# arduino_Uno_STIM_ShieldII_v4.net
KiCad netlist of a schematic drawn in EAGLE
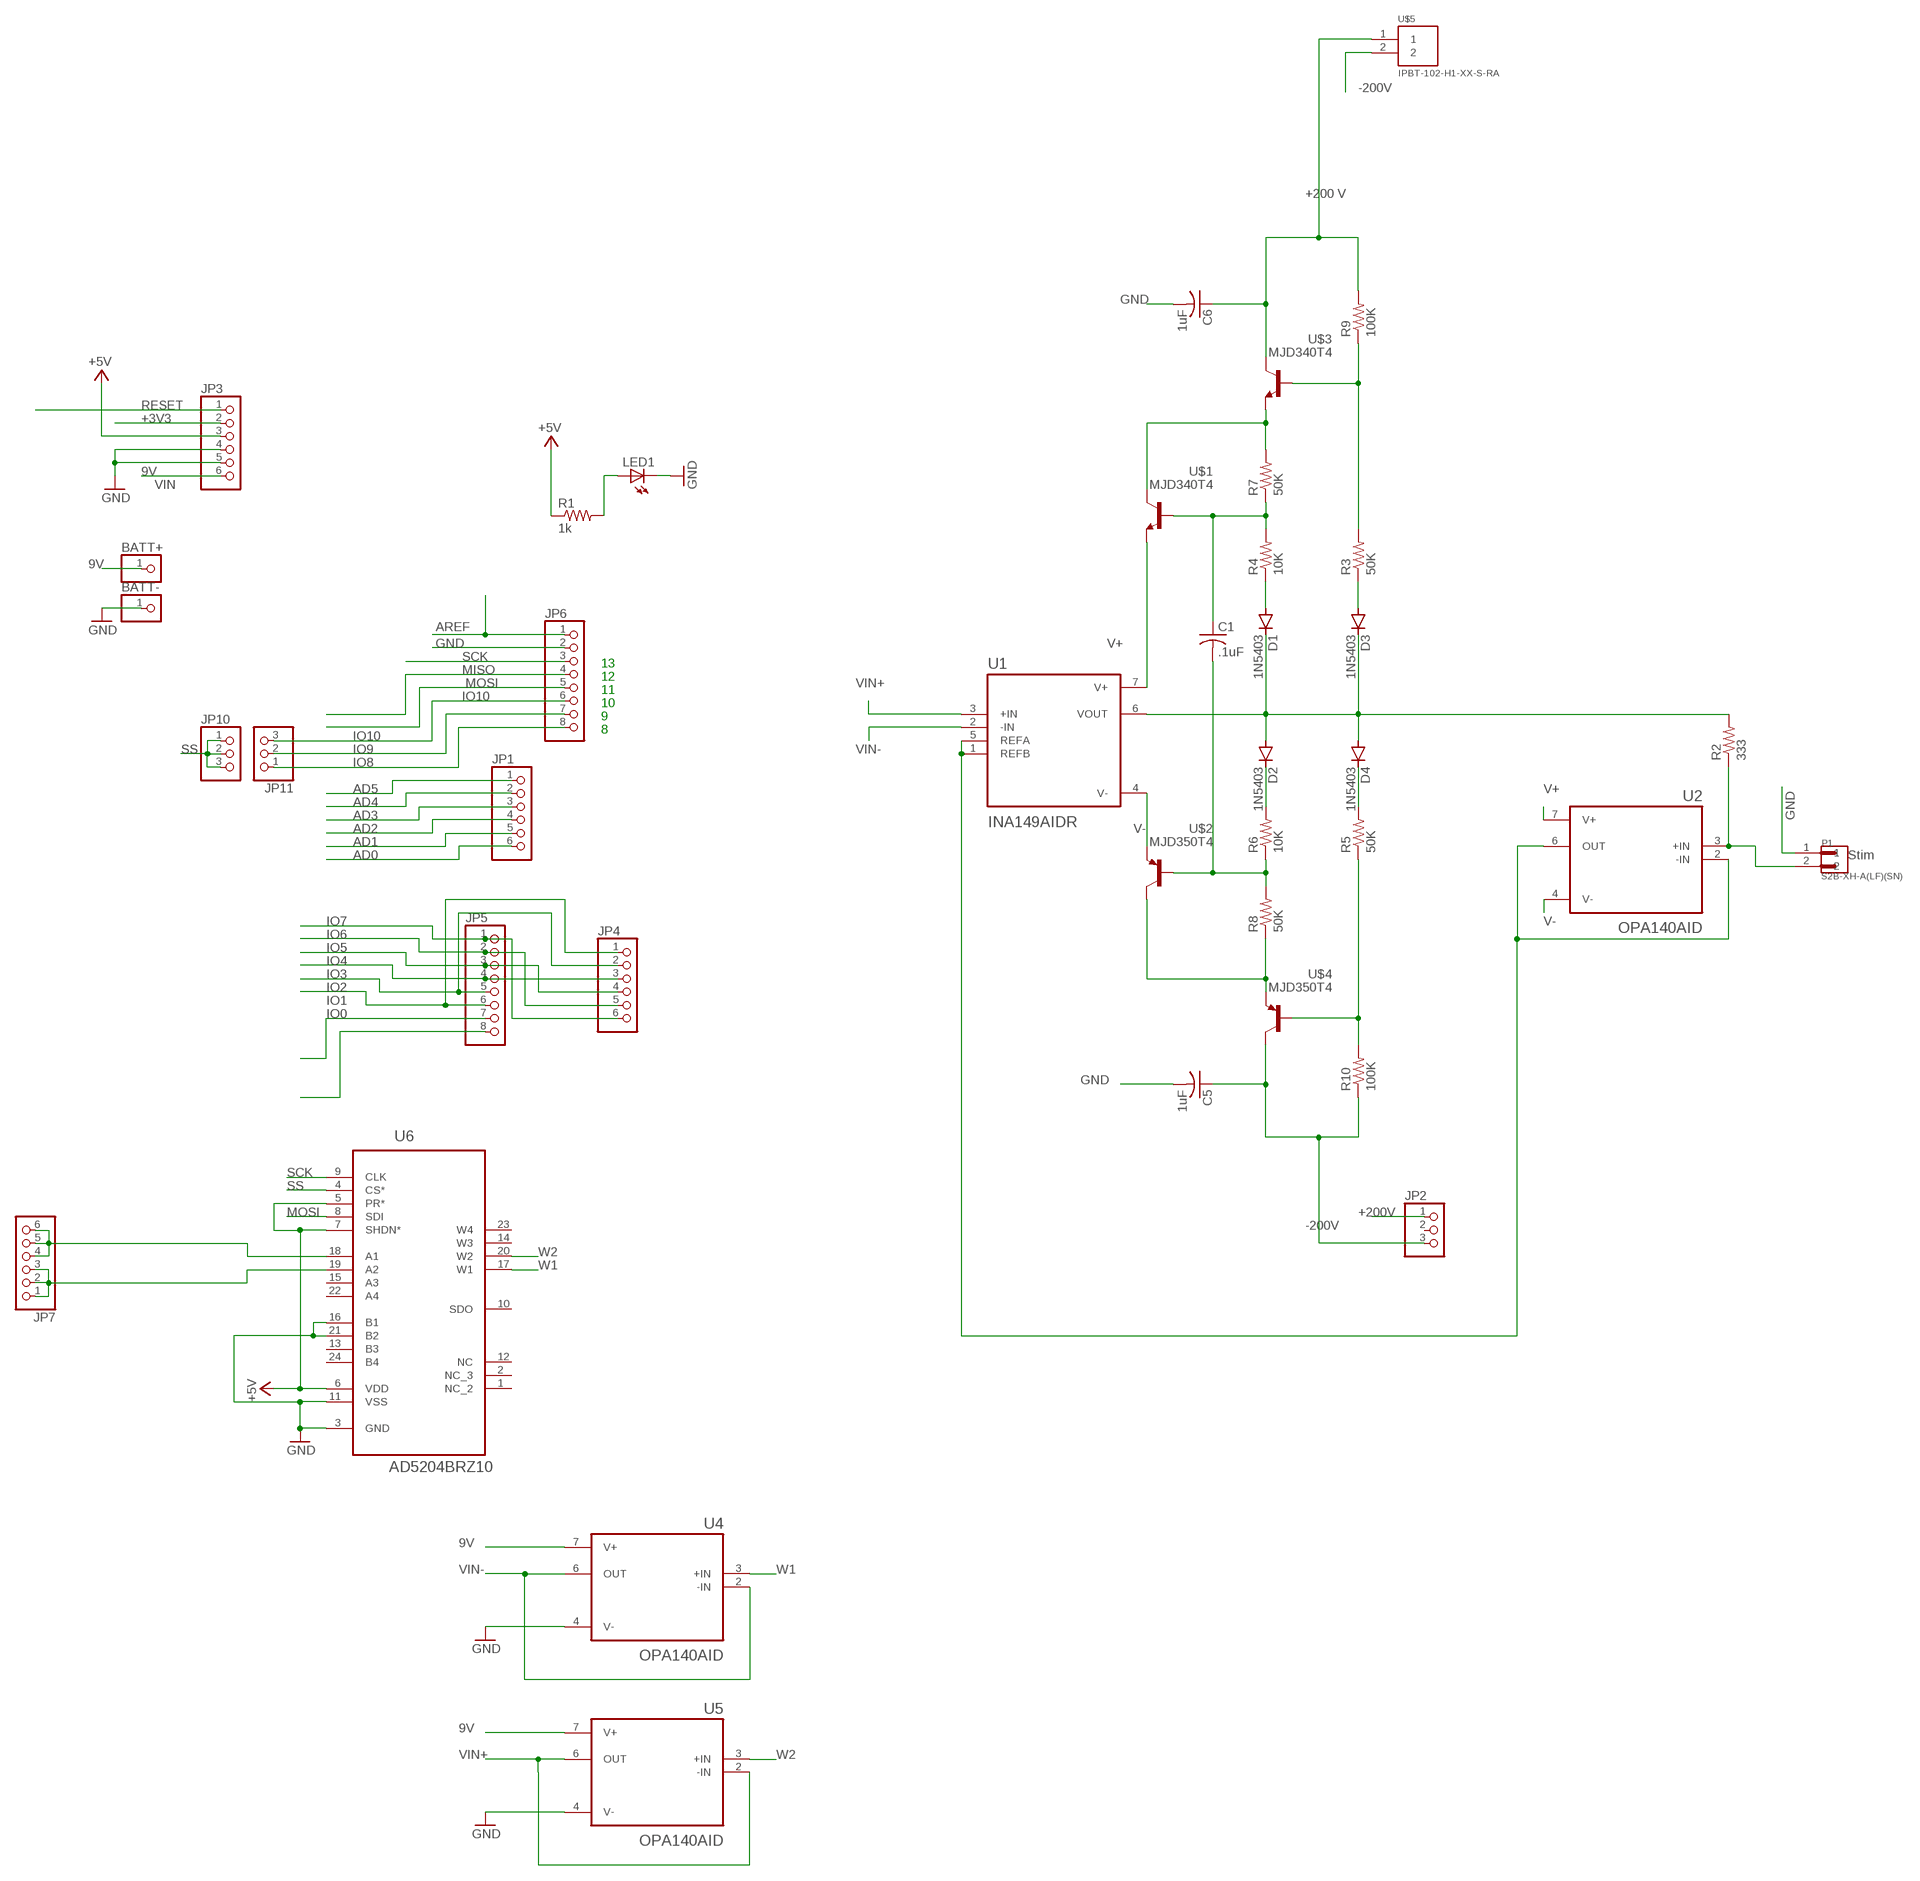
[diagram p0: schematic, sheet 1]

(export (version "E")
  (design (tool "Eeschema 10.0.6"))
  (components
    (comp (ref "BATT+")
      (value "PINHD-1X1")
      (footprint "eagle-import:1X01")
      (libsource (lib "eagle-import") (part "PINHD-1X1"))
    )
    (comp (ref "BATT-")
      (value "PINHD-1X1")
      (footprint "eagle-import:1X01")
      (libsource (lib "eagle-import") (part "PINHD-1X1"))
    )
    (comp (ref "C1")
      (value ".1uF")
      (footprint "eagle-import:C1206")
      (libsource (lib "eagle-import") (part "C-USC1206"))
    )
    (comp (ref "C5")
      (value "1uF")
      (footprint "eagle-import:C2220K")
      (libsource (lib "eagle-import") (part "C-USC2220K"))
    )
    (comp (ref "C6")
      (value "1uF")
      (footprint "eagle-import:C2220K")
      (libsource (lib "eagle-import") (part "C-USC2220K"))
    )
    (comp (ref "D1")
      (value "1N5403")
      (footprint "eagle-import:DO201-15")
      (libsource (lib "eagle-import") (part "1N5400"))
    )
    (comp (ref "D2")
      (value "1N5403")
      (footprint "eagle-import:DO201-15")
      (libsource (lib "eagle-import") (part "1N5400"))
    )
    (comp (ref "D3")
      (value "1N5403")
      (footprint "eagle-import:DO201-15")
      (libsource (lib "eagle-import") (part "1N5400"))
    )
    (comp (ref "D4")
      (value "1N5403")
      (footprint "eagle-import:DO201-15")
      (libsource (lib "eagle-import") (part "1N5400"))
    )
    (comp (ref "JP1")
      (value "PINHD-1X6CB")
      (footprint "eagle-import:1X06-CLEANBIG")
      (libsource (lib "eagle-import") (part "PINHD-1X6CB"))
    )
    (comp (ref "JP2")
      (value "PINHD-1X3")
      (footprint "eagle-import:1X03")
      (libsource (lib "eagle-import") (part "PINHD-1X3"))
    )
    (comp (ref "JP3")
      (value "PINHD-1X6CB")
      (footprint "eagle-import:1X06-CLEANBIG")
      (libsource (lib "eagle-import") (part "PINHD-1X6CB"))
    )
    (comp (ref "JP4")
      (value "PINHD-1X6CB")
      (footprint "eagle-import:1X06-CLEANBIG")
      (libsource (lib "eagle-import") (part "PINHD-1X6CB"))
    )
    (comp (ref "JP5")
      (value "PINHD-1X8CLEANBIG")
      (footprint "eagle-import:1X08-CLEANBIG")
      (libsource (lib "eagle-import") (part "PINHD-1X8CLEANBIG"))
    )
    (comp (ref "JP6")
      (value "PINHD-1X8CLEANBIG")
      (footprint "eagle-import:1X08-CLEANBIG")
      (libsource (lib "eagle-import") (part "PINHD-1X8CLEANBIG"))
    )
    (comp (ref "JP7")
      (value "PINHD-1X6CB")
      (footprint "eagle-import:1X06-CLEANBIG")
      (libsource (lib "eagle-import") (part "PINHD-1X6CB"))
    )
    (comp (ref "JP10")
      (value "PINHD-1X3CB")
      (footprint "eagle-import:1X03-CLEANBIG")
      (libsource (lib "eagle-import") (part "PINHD-1X3CB"))
    )
    (comp (ref "JP11")
      (value "PINHD-1X3CB")
      (footprint "eagle-import:1X03-CLEANBIG")
      (libsource (lib "eagle-import") (part "PINHD-1X3CB"))
    )
    (comp (ref "LED1")
      (value "LEDCHIPLED_1206")
      (footprint "eagle-import:CHIPLED_1206")
      (libsource (lib "eagle-import") (part "LEDCHIPLED_1206"))
    )
    (comp (ref "P1")
      (value "S2B-XH-A(LF)(SN)")
      (footprint "eagle-import:JST_S2B-XH-A(LF)(SN)")
      (fields (field (name "DIGI-KEY_PART_NUMBER") "455-2257-ND") (field (name "MF") "JST Sales"))
      (libsource (lib "eagle-import") (part "S2B-XH-A(LF)(SN)"))
    )
    (comp (ref "R1")
      (value "1k")
      (footprint "eagle-import:M0805")
      (libsource (lib "eagle-import") (part "R-US_M0805"))
    )
    (comp (ref "R2")
      (value "333")
      (footprint "eagle-import:M1206")
      (libsource (lib "eagle-import") (part "R-US_M1206"))
    )
    (comp (ref "R3")
      (value "50K")
      (footprint "eagle-import:M1206")
      (libsource (lib "eagle-import") (part "R-US_M1206"))
    )
    (comp (ref "R4")
      (value "10K")
      (footprint "eagle-import:M1206")
      (libsource (lib "eagle-import") (part "R-US_M1206"))
    )
    (comp (ref "R5")
      (value "50K")
      (footprint "eagle-import:M1206")
      (libsource (lib "eagle-import") (part "R-US_M1206"))
    )
    (comp (ref "R6")
      (value "10K")
      (footprint "eagle-import:M1206")
      (libsource (lib "eagle-import") (part "R-US_M1206"))
    )
    (comp (ref "R7")
      (value "50K")
      (footprint "eagle-import:M1206")
      (libsource (lib "eagle-import") (part "R-US_M1206"))
    )
    (comp (ref "R8")
      (value "50K")
      (footprint "eagle-import:M1206")
      (libsource (lib "eagle-import") (part "R-US_M1206"))
    )
    (comp (ref "R9")
      (value "100K")
      (footprint "eagle-import:M1206")
      (libsource (lib "eagle-import") (part "R-US_M1206"))
    )
    (comp (ref "R10")
      (value "100K")
      (footprint "eagle-import:M1206")
      (libsource (lib "eagle-import") (part "R-US_M1206"))
    )
    (comp (ref "U$1")
      (value "MJD340T4")
      (footprint "eagle-import:TO229P990X238-4N")
      (libsource (lib "eagle-import") (part "MJD340T4"))
    )
    (comp (ref "U$2")
      (value "MJD350T4")
      (footprint "eagle-import:TO229P990X238-4N")
      (libsource (lib "eagle-import") (part "MJD350T4"))
    )
    (comp (ref "U$3")
      (value "MJD340T4")
      (footprint "eagle-import:TO229P990X238-4N")
      (libsource (lib "eagle-import") (part "MJD340T4"))
    )
    (comp (ref "U$4")
      (value "MJD350T4")
      (footprint "eagle-import:TO229P990X238-4N")
      (libsource (lib "eagle-import") (part "MJD350T4"))
    )
    (comp (ref "U$5")
      (value "IPBT-102-H1-XX-S-RA")
      (footprint "eagle-import:IPBT-102-H1-XX-S-RA")
      (libsource (lib "eagle-import") (part "IPBT-102-H1-XX-S-RA"))
    )
    (comp (ref "U1")
      (value "INA149AIDR")
      (footprint "eagle-import:SOIC127P599X175-8N")
      (fields (field (name "MF") "Texas Instruments"))
      (libsource (lib "eagle-import") (part "INA149AIDR"))
    )
    (comp (ref "U2")
      (value "OPA140AID")
      (footprint "eagle-import:SOIC127P599X175-8N")
      (fields (field (name "MF") "Texas Instruments"))
      (libsource (lib "eagle-import") (part "OPA140AID"))
    )
    (comp (ref "U4")
      (value "OPA140AID")
      (footprint "eagle-import:SOIC127P599X175-8N")
      (fields (field (name "MF") "Texas Instruments"))
      (libsource (lib "eagle-import") (part "OPA140AID"))
    )
    (comp (ref "U5")
      (value "OPA140AID")
      (footprint "eagle-import:SOIC127P599X175-8N")
      (fields (field (name "MF") "Texas Instruments"))
      (libsource (lib "eagle-import") (part "OPA140AID"))
    )
    (comp (ref "U6")
      (value "AD5204BRZ10")
      (footprint "eagle-import:SOIC127P1032X265-24N")
      (fields (field (name "DIGI-KEY_PART_NUMBER") "AD5204BRZ100-ND") (field (name "MF") "Analog Devices"))
      (libsource (lib "eagle-import") (part "AD5204BRZ10"))
    )
  )
  (nets
    (net (code "1") (name "+5V") (class "Default")
      (node (ref "JP3") (pin "3") (pinfunction "3_3") (pintype "passive"))
      (node (ref "R1") (pin "1") (pinfunction "1_1") (pintype "passive"))
      (node (ref "U6") (pin "5") (pinfunction "PR*_5") (pintype "passive"))
      (node (ref "U6") (pin "6") (pinfunction "VDD_6") (pintype "power_in"))
      (node (ref "U6") (pin "7") (pinfunction "SHDN*_7") (pintype "passive"))
    )
    (net (code "2") (name "/+3V3") (class "Default")
      (node (ref "JP3") (pin "2") (pinfunction "2_2") (pintype "passive"))
    )
    (net (code "3") (name "/+200V") (class "Default")
      (node (ref "C6") (pin "1") (pinfunction "1_1") (pintype "passive"))
      (node (ref "JP2") (pin "1") (pinfunction "1_1") (pintype "passive"))
      (node (ref "R9") (pin "2") (pinfunction "2_2") (pintype "passive"))
      (node (ref "U$3") (pin "4") (pinfunction "C_4") (pintype "passive"))
      (node (ref "U$5") (pin "1") (pinfunction "1_1") (pintype "bidirectional"))
    )
    (net (code "4") (name "/-200V") (class "Default")
      (node (ref "C5") (pin "1") (pinfunction "1_1") (pintype "passive"))
      (node (ref "JP2") (pin "3") (pinfunction "3_3") (pintype "passive"))
      (node (ref "R10") (pin "1") (pinfunction "1_1") (pintype "passive"))
      (node (ref "U$4") (pin "4") (pinfunction "C_4") (pintype "passive"))
      (node (ref "U$5") (pin "2") (pinfunction "2_2") (pintype "bidirectional"))
    )
    (net (code "5") (name "/9V") (class "Default")
      (node (ref "BATT+") (pin "1") (pinfunction "1_1") (pintype "passive"))
      (node (ref "JP3") (pin "6") (pinfunction "6_6") (pintype "passive"))
      (node (ref "U4") (pin "7") (pinfunction "V+_7") (pintype "power_in"))
      (node (ref "U5") (pin "7") (pinfunction "V+_7") (pintype "power_in"))
    )
    (net (code "6") (name "/AD0") (class "Default")
      (node (ref "JP1") (pin "6") (pinfunction "6_6") (pintype "passive"))
    )
    (net (code "7") (name "/AD1") (class "Default")
      (node (ref "JP1") (pin "5") (pinfunction "5_5") (pintype "passive"))
    )
    (net (code "8") (name "/AD2") (class "Default")
      (node (ref "JP1") (pin "4") (pinfunction "4_4") (pintype "passive"))
    )
    (net (code "9") (name "/AD3") (class "Default")
      (node (ref "JP1") (pin "3") (pinfunction "3_3") (pintype "passive"))
    )
    (net (code "10") (name "/AD4") (class "Default")
      (node (ref "JP1") (pin "2") (pinfunction "2_2") (pintype "passive"))
    )
    (net (code "11") (name "/AD5") (class "Default")
      (node (ref "JP1") (pin "1") (pinfunction "1_1") (pintype "passive"))
    )
    (net (code "12") (name "/AREF") (class "Default")
      (node (ref "JP6") (pin "1") (pinfunction "1_1") (pintype "passive"))
    )
    (net (code "13") (name "/IO0") (class "Default")
      (node (ref "JP5") (pin "8") (pinfunction "8_8") (pintype "passive"))
    )
    (net (code "14") (name "/IO1") (class "Default")
      (node (ref "JP5") (pin "7") (pinfunction "7_7") (pintype "passive"))
    )
    (net (code "15") (name "/IO2") (class "Default")
      (node (ref "JP4") (pin "1") (pinfunction "1_1") (pintype "passive"))
      (node (ref "JP5") (pin "6") (pinfunction "6_6") (pintype "passive"))
    )
    (net (code "16") (name "/IO3") (class "Default")
      (node (ref "JP4") (pin "2") (pinfunction "2_2") (pintype "passive"))
      (node (ref "JP5") (pin "5") (pinfunction "5_5") (pintype "passive"))
    )
    (net (code "17") (name "/IO4") (class "Default")
      (node (ref "JP4") (pin "3") (pinfunction "3_3") (pintype "passive"))
      (node (ref "JP5") (pin "4") (pinfunction "4_4") (pintype "passive"))
    )
    (net (code "18") (name "/IO5") (class "Default")
      (node (ref "JP4") (pin "4") (pinfunction "4_4") (pintype "passive"))
      (node (ref "JP5") (pin "3") (pinfunction "3_3") (pintype "passive"))
    )
    (net (code "19") (name "/IO6") (class "Default")
      (node (ref "JP4") (pin "5") (pinfunction "5_5") (pintype "passive"))
      (node (ref "JP5") (pin "2") (pinfunction "2_2") (pintype "passive"))
    )
    (net (code "20") (name "/IO7") (class "Default")
      (node (ref "JP4") (pin "6") (pinfunction "6_6") (pintype "passive"))
      (node (ref "JP5") (pin "1") (pinfunction "1_1") (pintype "passive"))
    )
    (net (code "21") (name "/IO8") (class "Default")
      (node (ref "JP11") (pin "1") (pinfunction "1_1") (pintype "passive"))
      (node (ref "JP6") (pin "8") (pinfunction "8_8") (pintype "passive"))
    )
    (net (code "22") (name "/IO9") (class "Default")
      (node (ref "JP11") (pin "2") (pinfunction "2_2") (pintype "passive"))
      (node (ref "JP6") (pin "7") (pinfunction "7_7") (pintype "passive"))
    )
    (net (code "23") (name "/IO10") (class "Default")
      (node (ref "JP11") (pin "3") (pinfunction "3_3") (pintype "passive"))
      (node (ref "JP6") (pin "6") (pinfunction "6_6") (pintype "passive"))
    )
    (net (code "24") (name "/MISO") (class "Default")
      (node (ref "JP6") (pin "4") (pinfunction "4_4") (pintype "passive"))
    )
    (net (code "25") (name "/MOSI") (class "Default")
      (node (ref "JP6") (pin "5") (pinfunction "5_5") (pintype "passive"))
      (node (ref "U6") (pin "8") (pinfunction "SDI_8") (pintype "passive"))
    )
    (net (code "26") (name "/RESET") (class "Default")
      (node (ref "JP3") (pin "1") (pinfunction "1_1") (pintype "passive"))
    )
    (net (code "27") (name "/SCK") (class "Default")
      (node (ref "JP6") (pin "3") (pinfunction "3_3") (pintype "passive"))
      (node (ref "U6") (pin "9") (pinfunction "CLK_9") (pintype "passive"))
    )
    (net (code "28") (name "/SS") (class "Default")
      (node (ref "JP10") (pin "1") (pinfunction "1_1") (pintype "passive"))
      (node (ref "JP10") (pin "2") (pinfunction "2_2") (pintype "passive"))
      (node (ref "JP10") (pin "3") (pinfunction "3_3") (pintype "passive"))
      (node (ref "U6") (pin "4") (pinfunction "CS*_4") (pintype "passive"))
    )
    (net (code "29") (name "/V+") (class "Default")
      (node (ref "U$1") (pin "3") (pinfunction "E_3") (pintype "passive"))
      (node (ref "U1") (pin "7") (pinfunction "V+_7") (pintype "power_in"))
      (node (ref "U2") (pin "7") (pinfunction "V+_7") (pintype "power_in"))
    )
    (net (code "30") (name "/V-") (class "Default")
      (node (ref "U$2") (pin "3") (pinfunction "E_3") (pintype "passive"))
      (node (ref "U1") (pin "4") (pinfunction "V-_4") (pintype "power_in"))
      (node (ref "U2") (pin "4") (pinfunction "V-_4") (pintype "power_in"))
    )
    (net (code "31") (name "/VIN+") (class "Default")
      (node (ref "U1") (pin "3") (pinfunction "+IN_3") (pintype "input"))
      (node (ref "U5") (pin "2") (pinfunction "-IN_2") (pintype "input"))
      (node (ref "U5") (pin "6") (pinfunction "OUT_6") (pintype "output"))
    )
    (net (code "32") (name "/VIN-") (class "Default")
      (node (ref "U1") (pin "2") (pinfunction "-IN_2") (pintype "input"))
      (node (ref "U4") (pin "2") (pinfunction "-IN_2") (pintype "input"))
      (node (ref "U4") (pin "6") (pinfunction "OUT_6") (pintype "output"))
    )
    (net (code "33") (name "/W1") (class "Default")
      (node (ref "U4") (pin "3") (pinfunction "+IN_3") (pintype "input"))
      (node (ref "U6") (pin "17") (pinfunction "W1_17") (pintype "passive"))
    )
    (net (code "34") (name "/W2") (class "Default")
      (node (ref "U5") (pin "3") (pinfunction "+IN_3") (pintype "input"))
      (node (ref "U6") (pin "20") (pinfunction "W2_20") (pintype "passive"))
    )
    (net (code "35") (name "GND") (class "Default")
      (node (ref "BATT-") (pin "1") (pinfunction "1_1") (pintype "passive"))
      (node (ref "C5") (pin "2") (pinfunction "2_2") (pintype "passive"))
      (node (ref "C6") (pin "2") (pinfunction "2_2") (pintype "passive"))
      (node (ref "JP3") (pin "4") (pinfunction "4_4") (pintype "passive"))
      (node (ref "JP3") (pin "5") (pinfunction "5_5") (pintype "passive"))
      (node (ref "JP6") (pin "2") (pinfunction "2_2") (pintype "passive"))
      (node (ref "LED1") (pin "C") (pinfunction "C_C") (pintype "passive"))
      (node (ref "P1") (pin "1") (pinfunction "1_1") (pintype "passive"))
      (node (ref "U4") (pin "4") (pinfunction "V-_4") (pintype "power_in"))
      (node (ref "U5") (pin "4") (pinfunction "V-_4") (pintype "power_in"))
      (node (ref "U6") (pin "11") (pinfunction "VSS_11") (pintype "power_in"))
      (node (ref "U6") (pin "16") (pinfunction "B1_16") (pintype "passive"))
      (node (ref "U6") (pin "21") (pinfunction "B2_21") (pintype "passive"))
      (node (ref "U6") (pin "3") (pinfunction "GND_3") (pintype "passive"))
    )
    (net (code "36") (name "Net-(D1-PadA)") (class "Default")
      (node (ref "D1") (pin "A") (pinfunction "A_A") (pintype "passive"))
      (node (ref "R4") (pin "1") (pinfunction "1_1") (pintype "passive"))
    )
    (net (code "37") (name "Net-(D2-PadC)") (class "Default")
      (node (ref "D2") (pin "C") (pinfunction "C_C") (pintype "passive"))
      (node (ref "R6") (pin "2") (pinfunction "2_2") (pintype "passive"))
    )
    (net (code "38") (name "Net-(D3-PadA)") (class "Default")
      (node (ref "D3") (pin "A") (pinfunction "A_A") (pintype "passive"))
      (node (ref "R3") (pin "1") (pinfunction "1_1") (pintype "passive"))
    )
    (net (code "39") (name "Net-(D4-PadC)") (class "Default")
      (node (ref "D4") (pin "C") (pinfunction "C_C") (pintype "passive"))
      (node (ref "R5") (pin "2") (pinfunction "2_2") (pintype "passive"))
    )
    (net (code "40") (name "Net-(LED1-PadA)") (class "Default")
      (node (ref "LED1") (pin "A") (pinfunction "A_A") (pintype "passive"))
      (node (ref "R1") (pin "2") (pinfunction "2_2") (pintype "passive"))
    )
    (net (code "41") (name "Net-(U$1-B)") (class "Default")
      (node (ref "C1") (pin "1") (pinfunction "1_1") (pintype "passive"))
      (node (ref "R4") (pin "2") (pinfunction "2_2") (pintype "passive"))
      (node (ref "R7") (pin "1") (pinfunction "1_1") (pintype "passive"))
      (node (ref "U$1") (pin "1") (pinfunction "B_1") (pintype "passive"))
    )
    (net (code "42") (name "Net-(U$1-C)") (class "Default")
      (node (ref "R7") (pin "2") (pinfunction "2_2") (pintype "passive"))
      (node (ref "U$1") (pin "4") (pinfunction "C_4") (pintype "passive"))
      (node (ref "U$3") (pin "3") (pinfunction "E_3") (pintype "passive"))
    )
    (net (code "43") (name "Net-(U$2-B)") (class "Default")
      (node (ref "C1") (pin "2") (pinfunction "2_2") (pintype "passive"))
      (node (ref "R6") (pin "1") (pinfunction "1_1") (pintype "passive"))
      (node (ref "R8") (pin "2") (pinfunction "2_2") (pintype "passive"))
      (node (ref "U$2") (pin "1") (pinfunction "B_1") (pintype "passive"))
    )
    (net (code "44") (name "Net-(U$2-C)") (class "Default")
      (node (ref "R8") (pin "1") (pinfunction "1_1") (pintype "passive"))
      (node (ref "U$2") (pin "4") (pinfunction "C_4") (pintype "passive"))
      (node (ref "U$4") (pin "3") (pinfunction "E_3") (pintype "passive"))
    )
    (net (code "45") (name "Net-(U$3-B)") (class "Default")
      (node (ref "R3") (pin "2") (pinfunction "2_2") (pintype "passive"))
      (node (ref "R9") (pin "1") (pinfunction "1_1") (pintype "passive"))
      (node (ref "U$3") (pin "1") (pinfunction "B_1") (pintype "passive"))
    )
    (net (code "46") (name "Net-(U$4-B)") (class "Default")
      (node (ref "R10") (pin "2") (pinfunction "2_2") (pintype "passive"))
      (node (ref "R5") (pin "1") (pinfunction "1_1") (pintype "passive"))
      (node (ref "U$4") (pin "1") (pinfunction "B_1") (pintype "passive"))
    )
    (net (code "47") (name "Net-(U1-REFA)") (class "Default")
      (node (ref "U1") (pin "1") (pinfunction "REFB_1") (pintype "input"))
      (node (ref "U1") (pin "5") (pinfunction "REFA_5") (pintype "input"))
      (node (ref "U2") (pin "2") (pinfunction "-IN_2") (pintype "input"))
      (node (ref "U2") (pin "6") (pinfunction "OUT_6") (pintype "output"))
    )
    (net (code "48") (name "Net-(U1-VOUT)") (class "Default")
      (node (ref "D1") (pin "C") (pinfunction "C_C") (pintype "passive"))
      (node (ref "D2") (pin "A") (pinfunction "A_A") (pintype "passive"))
      (node (ref "D3") (pin "C") (pinfunction "C_C") (pintype "passive"))
      (node (ref "D4") (pin "A") (pinfunction "A_A") (pintype "passive"))
      (node (ref "R2") (pin "2") (pinfunction "2_2") (pintype "passive"))
      (node (ref "U1") (pin "6") (pinfunction "VOUT_6") (pintype "output"))
    )
    (net (code "49") (name "Net-(U2-+IN)") (class "Default")
      (node (ref "P1") (pin "2") (pinfunction "2_2") (pintype "passive"))
      (node (ref "R2") (pin "1") (pinfunction "1_1") (pintype "passive"))
      (node (ref "U2") (pin "3") (pinfunction "+IN_3") (pintype "input"))
    )
    (net (code "50") (name "Net-(U6-A1)") (class "Default")
      (node (ref "JP7") (pin "4") (pinfunction "4_4") (pintype "passive"))
      (node (ref "JP7") (pin "5") (pinfunction "5_5") (pintype "passive"))
      (node (ref "JP7") (pin "6") (pinfunction "6_6") (pintype "passive"))
      (node (ref "U6") (pin "18") (pinfunction "A1_18") (pintype "passive"))
    )
    (net (code "51") (name "Net-(U6-A2)") (class "Default")
      (node (ref "JP7") (pin "1") (pinfunction "1_1") (pintype "passive"))
      (node (ref "JP7") (pin "2") (pinfunction "2_2") (pintype "passive"))
      (node (ref "JP7") (pin "3") (pinfunction "3_3") (pintype "passive"))
      (node (ref "U6") (pin "19") (pinfunction "A2_19") (pintype "passive"))
    )
    (net (code "52") (name "unconnected-(JP2-Pad2)") (class "Default")
      (node (ref "JP2") (pin "2") (pinfunction "2_2") (pintype "passive"))
    )
    (net (code "53") (name "unconnected-(U6-A3-Pad15)") (class "Default")
      (node (ref "U6") (pin "15") (pinfunction "A3_15") (pintype "passive"))
    )
    (net (code "54") (name "unconnected-(U6-A4-Pad22)") (class "Default")
      (node (ref "U6") (pin "22") (pinfunction "A4_22") (pintype "passive"))
    )
    (net (code "55") (name "unconnected-(U6-B3-Pad13)") (class "Default")
      (node (ref "U6") (pin "13") (pinfunction "B3_13") (pintype "passive"))
    )
    (net (code "56") (name "unconnected-(U6-B4-Pad24)") (class "Default")
      (node (ref "U6") (pin "24") (pinfunction "B4_24") (pintype "passive"))
    )
    (net (code "57") (name "unconnected-(U6-NC-Pad12)") (class "Default")
      (node (ref "U6") (pin "12") (pinfunction "NC_12") (pintype "passive"))
    )
    (net (code "58") (name "unconnected-(U6-NC_2-Pad1)") (class "Default")
      (node (ref "U6") (pin "1") (pinfunction "NC_2_1") (pintype "passive"))
    )
    (net (code "59") (name "unconnected-(U6-NC_3-Pad2)") (class "Default")
      (node (ref "U6") (pin "2") (pinfunction "NC_3_2") (pintype "passive"))
    )
    (net (code "60") (name "unconnected-(U6-SDO-Pad10)") (class "Default")
      (node (ref "U6") (pin "10") (pinfunction "SDO_10") (pintype "passive"))
    )
    (net (code "61") (name "unconnected-(U6-W3-Pad14)") (class "Default")
      (node (ref "U6") (pin "14") (pinfunction "W3_14") (pintype "passive"))
    )
    (net (code "62") (name "unconnected-(U6-W4-Pad23)") (class "Default")
      (node (ref "U6") (pin "23") (pinfunction "W4_23") (pintype "passive"))
    )
  )
)
